# Sheet.net
KiCad netlist of a schematic drawn in Altium Designer
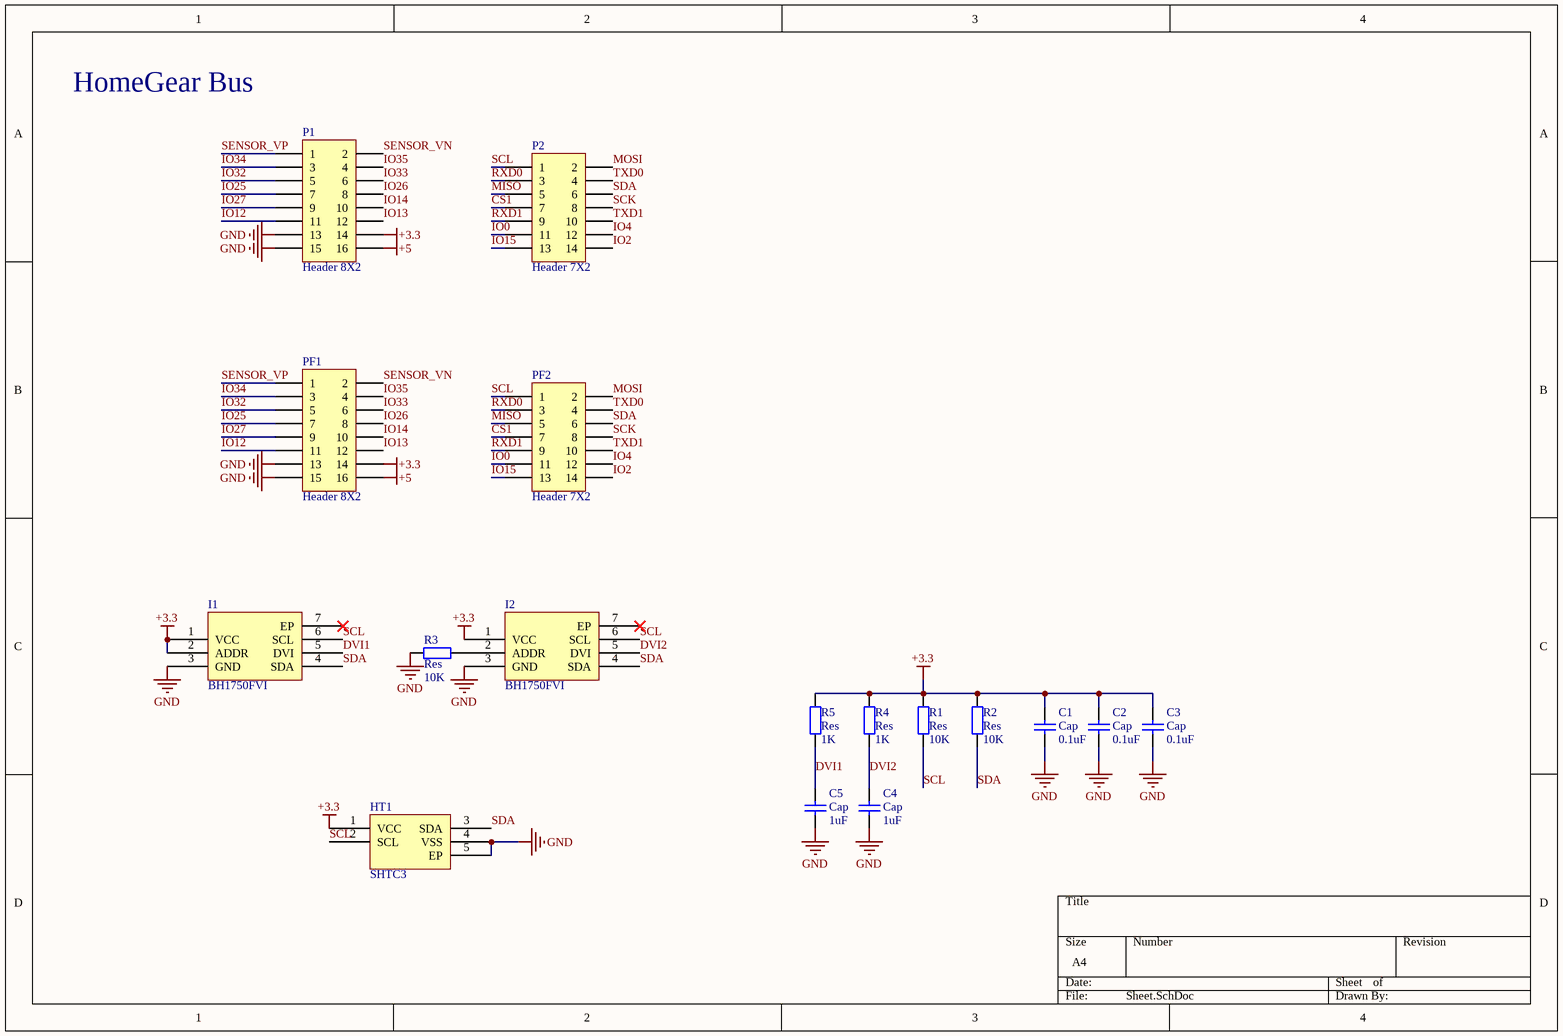
[diagram p0: Sheet.SchDoc]

(export (version "E")
  (design (tool "Eeschema 10.0.6"))
  (components
    (comp (ref "C1")
      (value "Cap")
      (footprint "MY0603")
      (description "Capacitor")
      (fields (field (name "ALTIUM_VALUE") "0.1uF") (field (name "PUBLISHER") "Altium Limited"))
      (libsource (lib "Miscellaneous Devices") (part "Cap"))
    )
    (comp (ref "C2")
      (value "Cap")
      (footprint "MY0603")
      (description "Capacitor")
      (fields (field (name "ALTIUM_VALUE") "0.1uF") (field (name "PUBLISHER") "Altium Limited"))
      (libsource (lib "Miscellaneous Devices") (part "Cap"))
    )
    (comp (ref "C3")
      (value "Cap")
      (footprint "MY0603")
      (description "Capacitor")
      (fields (field (name "ALTIUM_VALUE") "0.1uF") (field (name "PUBLISHER") "Altium Limited"))
      (libsource (lib "Miscellaneous Devices") (part "Cap"))
    )
    (comp (ref "C4")
      (value "Cap")
      (footprint "MY0603")
      (description "Capacitor")
      (fields (field (name "ALTIUM_VALUE") "1uF") (field (name "PUBLISHER") "Altium Limited"))
      (libsource (lib "Miscellaneous Devices") (part "Cap"))
    )
    (comp (ref "C5")
      (value "Cap")
      (footprint "MY0603")
      (description "Capacitor")
      (fields (field (name "ALTIUM_VALUE") "1uF") (field (name "PUBLISHER") "Altium Limited"))
      (libsource (lib "Miscellaneous Devices") (part "Cap"))
    )
    (comp (ref "HT1") (value "SHTC3") (footprint "SHTC3") (libsource (lib "我的元件库") (part "SHTC3")))
    (comp (ref "I1")
      (value "BH1750FVI")
      (footprint "BH1750_SMD")
      (libsource (lib "我的元件库") (part "BH1750FVI"))
    )
    (comp (ref "I2")
      (value "BH1750FVI")
      (footprint "BH1750_SMD")
      (libsource (lib "我的元件库") (part "BH1750FVI"))
    )
    (comp (ref "P1")
      (value "Header 8X2")
      (footprint "SMD_PIN_HDR8x2_2.0MM")
      (description "Header, 8-Pin, Dual row")
      (fields (field (name "PUBLISHER") "Altium Limited"))
      (libsource (lib "Miscellaneous Connectors") (part "Header 8X2"))
    )
    (comp (ref "P2")
      (value "Header 7X2")
      (footprint "SMD_PIN_HDR7x2_2.0MM")
      (description "Header, 7-Pin, Dual row")
      (fields (field (name "PUBLISHER") "Altium Limited"))
      (libsource (lib "Miscellaneous Connectors") (part "Header 7X2"))
    )
    (comp (ref "PF1")
      (value "Header 8X2")
      (footprint "SMD_FEM_HDR8x2_2.0MM")
      (description "Header, 8-Pin, Dual row")
      (fields (field (name "PUBLISHER") "Altium Limited"))
      (libsource (lib "Miscellaneous Connectors") (part "Header 8X2"))
    )
    (comp (ref "PF2")
      (value "Header 7X2")
      (footprint "SMD_FEM_HDR7x2_2.0MM")
      (description "Header, 7-Pin, Dual row")
      (fields (field (name "PUBLISHER") "Altium Limited"))
      (libsource (lib "Miscellaneous Connectors") (part "Header 7X2"))
    )
    (comp (ref "R1")
      (value "Res")
      (footprint "MY0603")
      (description "Resistor")
      (fields (field (name "ALTIUM_VALUE") "10K") (field (name "PUBLISHER") "Altium Limited"))
      (libsource (lib "Miscellaneous Devices") (part "Res2"))
    )
    (comp (ref "R2")
      (value "Res")
      (footprint "MY0603")
      (description "Resistor")
      (fields (field (name "ALTIUM_VALUE") "10K") (field (name "PUBLISHER") "Altium Limited"))
      (libsource (lib "Miscellaneous Devices") (part "Res2"))
    )
    (comp (ref "R3")
      (value "Res")
      (footprint "MY0603")
      (description "Resistor")
      (fields (field (name "ALTIUM_VALUE") "10K") (field (name "PUBLISHER") "Altium Limited"))
      (libsource (lib "") (part "Res2_1"))
    )
    (comp (ref "R4")
      (value "Res")
      (footprint "MY0603")
      (description "Resistor")
      (fields (field (name "ALTIUM_VALUE") "1K") (field (name "PUBLISHER") "Altium Limited"))
      (libsource (lib "Miscellaneous Devices") (part "Res2"))
    )
    (comp (ref "R5")
      (value "Res")
      (footprint "MY0603")
      (description "Resistor")
      (fields (field (name "ALTIUM_VALUE") "1K") (field (name "PUBLISHER") "Altium Limited"))
      (libsource (lib "Miscellaneous Devices") (part "Res2"))
    )
  )
  (nets
    (net (code "1") (name "+3.3") (class "Default")
      (node (ref "C1") (pin "2") (pinfunction "2_2") (pintype "passive"))
      (node (ref "C2") (pin "2") (pinfunction "2_2") (pintype "passive"))
      (node (ref "C3") (pin "2") (pinfunction "2_2") (pintype "passive"))
      (node (ref "HT1") (pin "1") (pinfunction "VCC_1") (pintype "passive"))
      (node (ref "I1") (pin "1") (pinfunction "VCC_1") (pintype "passive"))
      (node (ref "I1") (pin "2") (pinfunction "ADDR_2") (pintype "passive"))
      (node (ref "I2") (pin "1") (pinfunction "VCC_1") (pintype "passive"))
      (node (ref "P1") (pin "14") (pinfunction "14_14") (pintype "passive"))
      (node (ref "PF1") (pin "14") (pinfunction "14_14") (pintype "passive"))
      (node (ref "R1") (pin "2") (pinfunction "2_2") (pintype "passive"))
      (node (ref "R2") (pin "2") (pinfunction "2_2") (pintype "passive"))
      (node (ref "R4") (pin "2") (pinfunction "2_2") (pintype "passive"))
      (node (ref "R5") (pin "2") (pinfunction "2_2") (pintype "passive"))
    )
    (net (code "2") (name "+5") (class "Default")
      (node (ref "P1") (pin "16") (pinfunction "16_16") (pintype "passive"))
      (node (ref "PF1") (pin "16") (pinfunction "16_16") (pintype "passive"))
    )
    (net (code "3") (name "/CS1") (class "Default")
      (node (ref "P2") (pin "7") (pinfunction "7_7") (pintype "passive"))
      (node (ref "PF2") (pin "7") (pinfunction "7_7") (pintype "passive"))
    )
    (net (code "4") (name "/DVI1") (class "Default")
      (node (ref "C5") (pin "2") (pinfunction "2_2") (pintype "passive"))
      (node (ref "I1") (pin "5") (pinfunction "DVI_5") (pintype "passive"))
      (node (ref "R5") (pin "1") (pinfunction "1_1") (pintype "passive"))
    )
    (net (code "5") (name "/DVI2") (class "Default")
      (node (ref "C4") (pin "2") (pinfunction "2_2") (pintype "passive"))
      (node (ref "I2") (pin "5") (pinfunction "DVI_5") (pintype "passive"))
      (node (ref "R4") (pin "1") (pinfunction "1_1") (pintype "passive"))
    )
    (net (code "6") (name "/IO0") (class "Default")
      (node (ref "P2") (pin "11") (pinfunction "11_11") (pintype "passive"))
      (node (ref "PF2") (pin "11") (pinfunction "11_11") (pintype "passive"))
    )
    (net (code "7") (name "/IO2") (class "Default")
      (node (ref "P2") (pin "14") (pinfunction "14_14") (pintype "passive"))
      (node (ref "PF2") (pin "14") (pinfunction "14_14") (pintype "passive"))
    )
    (net (code "8") (name "/IO4") (class "Default")
      (node (ref "P2") (pin "12") (pinfunction "12_12") (pintype "passive"))
      (node (ref "PF2") (pin "12") (pinfunction "12_12") (pintype "passive"))
    )
    (net (code "9") (name "/IO12") (class "Default")
      (node (ref "P1") (pin "11") (pinfunction "11_11") (pintype "passive"))
      (node (ref "PF1") (pin "11") (pinfunction "11_11") (pintype "passive"))
    )
    (net (code "10") (name "/IO13") (class "Default")
      (node (ref "P1") (pin "12") (pinfunction "12_12") (pintype "passive"))
      (node (ref "PF1") (pin "12") (pinfunction "12_12") (pintype "passive"))
    )
    (net (code "11") (name "/IO14") (class "Default")
      (node (ref "P1") (pin "10") (pinfunction "10_10") (pintype "passive"))
      (node (ref "PF1") (pin "10") (pinfunction "10_10") (pintype "passive"))
    )
    (net (code "12") (name "/IO15") (class "Default")
      (node (ref "P2") (pin "13") (pinfunction "13_13") (pintype "passive"))
      (node (ref "PF2") (pin "13") (pinfunction "13_13") (pintype "passive"))
    )
    (net (code "13") (name "/IO25") (class "Default")
      (node (ref "P1") (pin "7") (pinfunction "7_7") (pintype "passive"))
      (node (ref "PF1") (pin "7") (pinfunction "7_7") (pintype "passive"))
    )
    (net (code "14") (name "/IO26") (class "Default")
      (node (ref "P1") (pin "8") (pinfunction "8_8") (pintype "passive"))
      (node (ref "PF1") (pin "8") (pinfunction "8_8") (pintype "passive"))
    )
    (net (code "15") (name "/IO27") (class "Default")
      (node (ref "P1") (pin "9") (pinfunction "9_9") (pintype "passive"))
      (node (ref "PF1") (pin "9") (pinfunction "9_9") (pintype "passive"))
    )
    (net (code "16") (name "/IO32") (class "Default")
      (node (ref "P1") (pin "5") (pinfunction "5_5") (pintype "passive"))
      (node (ref "PF1") (pin "5") (pinfunction "5_5") (pintype "passive"))
    )
    (net (code "17") (name "/IO33") (class "Default")
      (node (ref "P1") (pin "6") (pinfunction "6_6") (pintype "passive"))
      (node (ref "PF1") (pin "6") (pinfunction "6_6") (pintype "passive"))
    )
    (net (code "18") (name "/IO34") (class "Default")
      (node (ref "P1") (pin "3") (pinfunction "3_3") (pintype "passive"))
      (node (ref "PF1") (pin "3") (pinfunction "3_3") (pintype "passive"))
    )
    (net (code "19") (name "/IO35") (class "Default")
      (node (ref "P1") (pin "4") (pinfunction "4_4") (pintype "passive"))
      (node (ref "PF1") (pin "4") (pinfunction "4_4") (pintype "passive"))
    )
    (net (code "20") (name "/MISO") (class "Default")
      (node (ref "P2") (pin "5") (pinfunction "5_5") (pintype "passive"))
      (node (ref "PF2") (pin "5") (pinfunction "5_5") (pintype "passive"))
    )
    (net (code "21") (name "/MOSI") (class "Default")
      (node (ref "P2") (pin "2") (pinfunction "2_2") (pintype "passive"))
      (node (ref "PF2") (pin "2") (pinfunction "2_2") (pintype "passive"))
    )
    (net (code "22") (name "/RXD0") (class "Default")
      (node (ref "P2") (pin "3") (pinfunction "3_3") (pintype "passive"))
      (node (ref "PF2") (pin "3") (pinfunction "3_3") (pintype "passive"))
    )
    (net (code "23") (name "/RXD1") (class "Default")
      (node (ref "P2") (pin "9") (pinfunction "9_9") (pintype "passive"))
      (node (ref "PF2") (pin "9") (pinfunction "9_9") (pintype "passive"))
    )
    (net (code "24") (name "/SCK") (class "Default")
      (node (ref "P2") (pin "8") (pinfunction "8_8") (pintype "passive"))
      (node (ref "PF2") (pin "8") (pinfunction "8_8") (pintype "passive"))
    )
    (net (code "25") (name "/SCL") (class "Default")
      (node (ref "HT1") (pin "2") (pinfunction "SCL_2") (pintype "passive"))
      (node (ref "I1") (pin "6") (pinfunction "SCL_6") (pintype "passive"))
      (node (ref "I2") (pin "6") (pinfunction "SCL_6") (pintype "passive"))
      (node (ref "P2") (pin "1") (pinfunction "1_1") (pintype "passive"))
      (node (ref "PF2") (pin "1") (pinfunction "1_1") (pintype "passive"))
      (node (ref "R1") (pin "1") (pinfunction "1_1") (pintype "passive"))
    )
    (net (code "26") (name "/SDA") (class "Default")
      (node (ref "HT1") (pin "3") (pinfunction "SDA_3") (pintype "passive"))
      (node (ref "I1") (pin "4") (pinfunction "SDA_4") (pintype "passive"))
      (node (ref "I2") (pin "4") (pinfunction "SDA_4") (pintype "passive"))
      (node (ref "P2") (pin "6") (pinfunction "6_6") (pintype "passive"))
      (node (ref "PF2") (pin "6") (pinfunction "6_6") (pintype "passive"))
      (node (ref "R2") (pin "1") (pinfunction "1_1") (pintype "passive"))
    )
    (net (code "27") (name "/SENSOR_VN") (class "Default")
      (node (ref "P1") (pin "2") (pinfunction "2_2") (pintype "passive"))
      (node (ref "PF1") (pin "2") (pinfunction "2_2") (pintype "passive"))
    )
    (net (code "28") (name "/SENSOR_VP") (class "Default")
      (node (ref "P1") (pin "1") (pinfunction "1_1") (pintype "passive"))
      (node (ref "PF1") (pin "1") (pinfunction "1_1") (pintype "passive"))
    )
    (net (code "29") (name "/TXD0") (class "Default")
      (node (ref "P2") (pin "4") (pinfunction "4_4") (pintype "passive"))
      (node (ref "PF2") (pin "4") (pinfunction "4_4") (pintype "passive"))
    )
    (net (code "30") (name "/TXD1") (class "Default")
      (node (ref "P2") (pin "10") (pinfunction "10_10") (pintype "passive"))
      (node (ref "PF2") (pin "10") (pinfunction "10_10") (pintype "passive"))
    )
    (net (code "31") (name "GND") (class "Default")
      (node (ref "C1") (pin "1") (pinfunction "1_1") (pintype "passive"))
      (node (ref "C2") (pin "1") (pinfunction "1_1") (pintype "passive"))
      (node (ref "C3") (pin "1") (pinfunction "1_1") (pintype "passive"))
      (node (ref "C4") (pin "1") (pinfunction "1_1") (pintype "passive"))
      (node (ref "C5") (pin "1") (pinfunction "1_1") (pintype "passive"))
      (node (ref "HT1") (pin "4") (pinfunction "VSS_4") (pintype "passive"))
      (node (ref "HT1") (pin "5") (pinfunction "EP_5") (pintype "passive"))
      (node (ref "I1") (pin "3") (pinfunction "GND_3") (pintype "passive"))
      (node (ref "I2") (pin "3") (pinfunction "GND_3") (pintype "passive"))
      (node (ref "P1") (pin "13") (pinfunction "13_13") (pintype "passive"))
      (node (ref "P1") (pin "15") (pinfunction "15_15") (pintype "passive"))
      (node (ref "PF1") (pin "13") (pinfunction "13_13") (pintype "passive"))
      (node (ref "PF1") (pin "15") (pinfunction "15_15") (pintype "passive"))
      (node (ref "R3") (pin "2") (pinfunction "2_2") (pintype "passive"))
    )
    (net (code "32") (name "Net-(I2-ADDR)") (class "Default")
      (node (ref "I2") (pin "2") (pinfunction "ADDR_2") (pintype "passive"))
      (node (ref "R3") (pin "1") (pinfunction "1_1") (pintype "passive"))
    )
    (net (code "33") (name "unconnected-(I1-EP-Pad7)") (class "Default")
      (node (ref "I1") (pin "7") (pinfunction "EP_7") (pintype "passive+no_connect"))
    )
    (net (code "34") (name "unconnected-(I2-EP-Pad7)") (class "Default")
      (node (ref "I2") (pin "7") (pinfunction "EP_7") (pintype "passive+no_connect"))
    )
  )
)
